# preamp.net
KiCad netlist of a schematic drawn in EAGLE
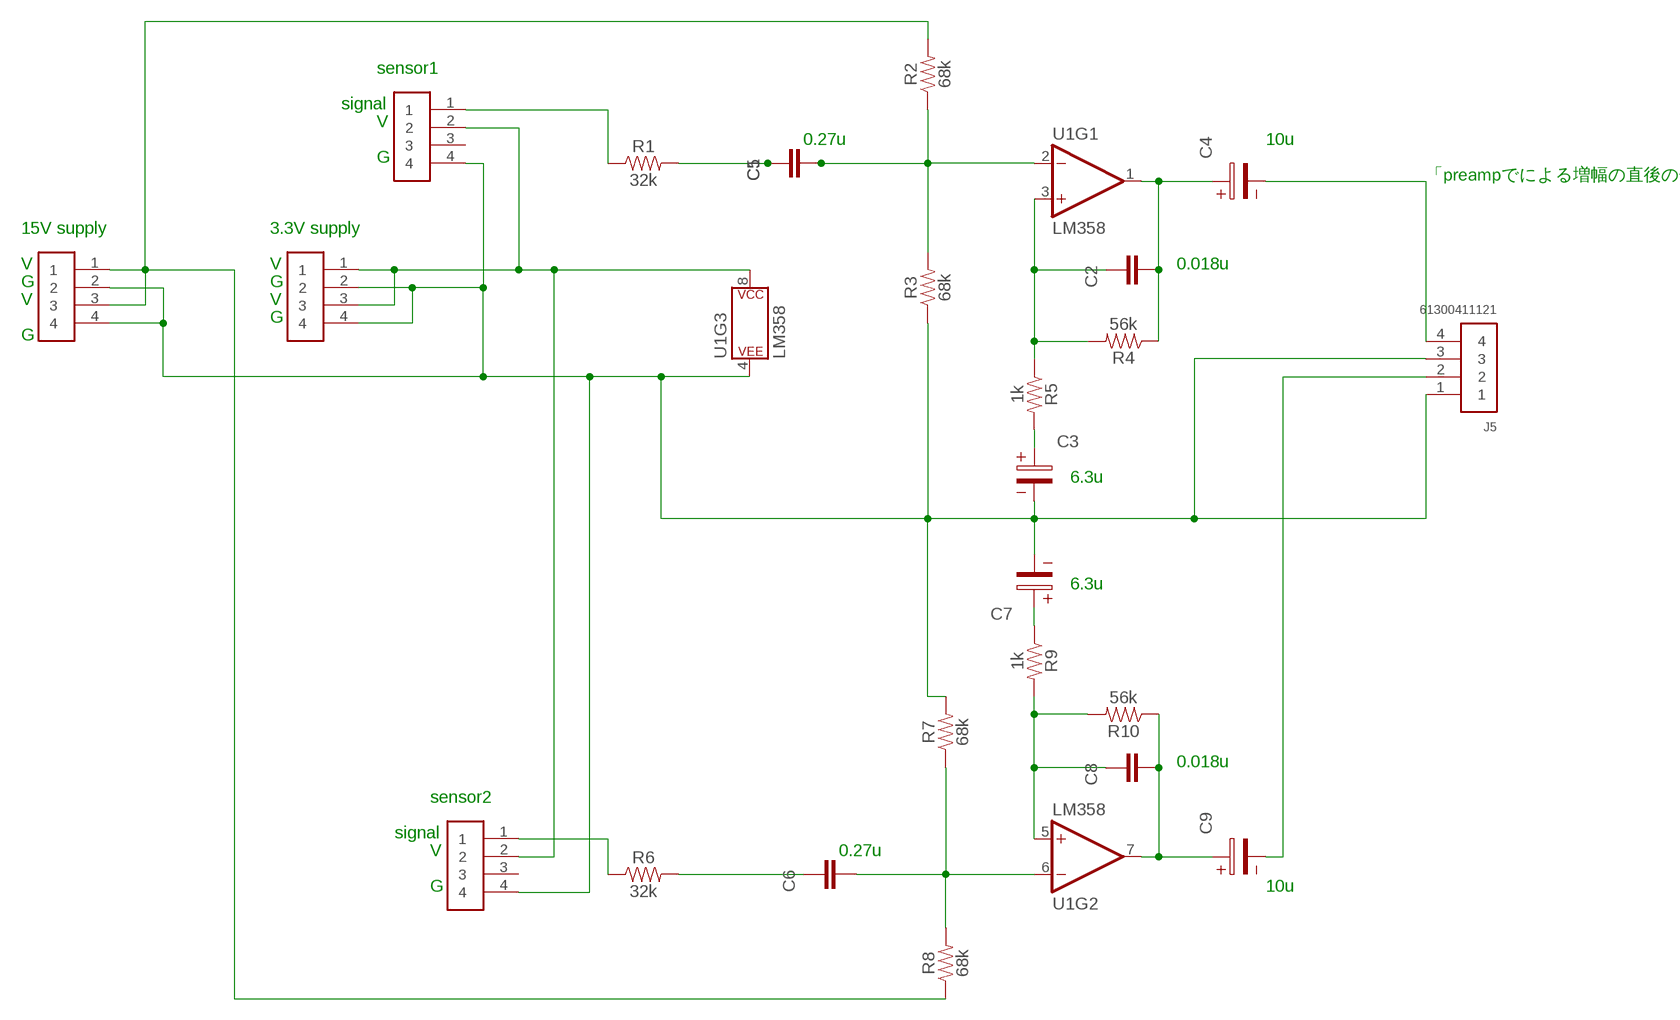
[diagram p0: schematic, sheet 1]

(export (version "E")
  (design (tool "Eeschema 10.0.6"))
  (components
    (comp (ref "C1")
      (value "CC0603JRNPO9BN270")
      (footprint "eagle-import:CAP_0603")
      (fields
        (field (name "DIGIKEY_PART_NUMBER") "311-1063-2-ND")
        (field (name "MANUFACTURER") "Yageo")
        (field (name "CREATED_BY") "PCBLayout.com")
      )
      (libsource (lib "eagle-import") (part "CC0603JRNPO9BN270"))
    )
    (comp (ref "C2")
      (value "0.018u")
      (footprint "eagle-import:CAP_0603")
      (fields
        (field (name "DIGIKEY_PART_NUMBER") "311-1063-2-ND")
        (field (name "MANUFACTURER") "Yageo")
        (field (name "MPN") "CC0603JRNPO9BN270")
        (field (name "CREATED_BY") "PCBLayout.com")
      )
      (libsource (lib "eagle-import") (part "CC0603JRNPO9BN270"))
    )
    (comp (ref "C3")
      (value "WCAP-AI3H_25X30_861141084008")
      (footprint "eagle-import:25X10X2(DXPXΦ)")
      (libsource (lib "eagle-import") (part "WCAP-AI3H_861141084008_25X30"))
    )
    (comp (ref "C4")
      (value "WCAP-AI3H_25X30_861141084008")
      (footprint "eagle-import:25X10X2(DXPXΦ)")
      (libsource (lib "eagle-import") (part "WCAP-AI3H_861141084008_25X30"))
    )
    (comp (ref "C5")
      (value "0.27u")
      (footprint "eagle-import:CAP_0603")
      (fields
        (field (name "DIGIKEY_PART_NUMBER") "311-1063-2-ND")
        (field (name "MANUFACTURER") "Yageo")
        (field (name "MPN") "CC0603JRNPO9BN270")
        (field (name "CREATED_BY") "PCBLayout.com")
      )
      (libsource (lib "eagle-import") (part "CC0603JRNPO9BN270"))
    )
    (comp (ref "C6")
      (value "CC0603JRNPO9BN270")
      (footprint "eagle-import:CAP_0603")
      (fields
        (field (name "DIGIKEY_PART_NUMBER") "311-1063-2-ND")
        (field (name "MANUFACTURER") "Yageo")
        (field (name "CREATED_BY") "PCBLayout.com")
      )
      (libsource (lib "eagle-import") (part "CC0603JRNPO9BN270"))
    )
    (comp (ref "C7")
      (value "WCAP-AI3H_25X30_861141084008")
      (footprint "eagle-import:25X10X2(DXPXΦ)")
      (libsource (lib "eagle-import") (part "WCAP-AI3H_861141084008_25X30"))
    )
    (comp (ref "C8")
      (value "CC0603JRNPO9BN270")
      (footprint "eagle-import:CAP_0603")
      (fields
        (field (name "DIGIKEY_PART_NUMBER") "311-1063-2-ND")
        (field (name "MANUFACTURER") "Yageo")
        (field (name "CREATED_BY") "PCBLayout.com")
      )
      (libsource (lib "eagle-import") (part "CC0603JRNPO9BN270"))
    )
    (comp (ref "C9")
      (value "WCAP-AI3H_25X30_861141084008")
      (footprint "eagle-import:25X10X2(DXPXΦ)")
      (libsource (lib "eagle-import") (part "WCAP-AI3H_861141084008_25X30"))
    )
    (comp (ref "J1")
      (value "61300411121")
      (footprint "eagle-import:61300411121")
      (fields
        (field (name "DIGI_KEY_PART_NUMBER") "732-5317-ND")
        (field (name "MANUFACTURER") "Wurth Electronics Inc.")
        (field (name "CREATED_BY") "PCBLayout.com")
      )
      (libsource (lib "eagle-import") (part "61300411121"))
    )
    (comp (ref "J2")
      (value "61300411121")
      (footprint "eagle-import:61300411121")
      (fields
        (field (name "DIGI_KEY_PART_NUMBER") "732-5317-ND")
        (field (name "MANUFACTURER") "Wurth Electronics Inc.")
        (field (name "CREATED_BY") "PCBLayout.com")
      )
      (libsource (lib "eagle-import") (part "61300411121"))
    )
    (comp (ref "J3")
      (value "61300411121")
      (footprint "eagle-import:61300411121")
      (fields
        (field (name "DIGI_KEY_PART_NUMBER") "732-5317-ND")
        (field (name "MANUFACTURER") "Wurth Electronics Inc.")
        (field (name "CREATED_BY") "PCBLayout.com")
      )
      (libsource (lib "eagle-import") (part "61300411121"))
    )
    (comp (ref "J4")
      (value "61300411121")
      (footprint "eagle-import:61300411121")
      (fields
        (field (name "DIGI_KEY_PART_NUMBER") "732-5317-ND")
        (field (name "MANUFACTURER") "Wurth Electronics Inc.")
        (field (name "CREATED_BY") "PCBLayout.com")
      )
      (libsource (lib "eagle-import") (part "61300411121"))
    )
    (comp (ref "J5")
      (value "61300411121")
      (footprint "eagle-import:61300411121")
      (fields
        (field (name "DIGI_KEY_PART_NUMBER") "732-5317-ND")
        (field (name "MANUFACTURER") "Wurth Electronics Inc.")
        (field (name "CREATED_BY") "PCBLayout.com")
      )
      (libsource (lib "eagle-import") (part "61300411121"))
    )
    (comp (ref "R1")
      (value "32k")
      (footprint "eagle-import:AXIAL-0.3")
      (libsource (lib "eagle-import") (part "10MOHM-HORIZ-1/4W-5%"))
    )
    (comp (ref "R2")
      (value "68k")
      (footprint "eagle-import:AXIAL-0.3")
      (libsource (lib "eagle-import") (part "10MOHM-HORIZ-1/4W-5%"))
    )
    (comp (ref "R3")
      (value "68k")
      (footprint "eagle-import:AXIAL-0.3")
      (libsource (lib "eagle-import") (part "10MOHM-HORIZ-1/4W-5%"))
    )
    (comp (ref "R4")
      (value "56k")
      (footprint "eagle-import:AXIAL-0.3")
      (libsource (lib "eagle-import") (part "10MOHM-HORIZ-1/4W-5%"))
    )
    (comp (ref "R5")
      (value "1k")
      (footprint "eagle-import:AXIAL-0.3")
      (libsource (lib "eagle-import") (part "10MOHM-HORIZ-1/4W-5%"))
    )
    (comp (ref "R6")
      (value "32k")
      (footprint "eagle-import:AXIAL-0.3")
      (libsource (lib "eagle-import") (part "10MOHM-HORIZ-1/4W-5%"))
    )
    (comp (ref "R7")
      (value "68k")
      (footprint "eagle-import:AXIAL-0.3")
      (libsource (lib "eagle-import") (part "10MOHM-HORIZ-1/4W-5%"))
    )
    (comp (ref "R8")
      (value "68k")
      (footprint "eagle-import:AXIAL-0.3")
      (libsource (lib "eagle-import") (part "10MOHM-HORIZ-1/4W-5%"))
    )
    (comp (ref "R9")
      (value "1k")
      (footprint "eagle-import:AXIAL-0.3")
      (libsource (lib "eagle-import") (part "10MOHM-HORIZ-1/4W-5%"))
    )
    (comp (ref "R10")
      (value "56k")
      (footprint "eagle-import:AXIAL-0.3")
      (libsource (lib "eagle-import") (part "10MOHM-HORIZ-1/4W-5%"))
    )
    (comp (ref "U1")
      (value "LM358")
      (footprint "eagle-import:DIP08")
      (libsource (lib "eagle-import") (part "LM358"))
    )
  )
  (nets
    (net (code "1") (name "Net-(C4-Pad2)") (class "Default")
      (node (ref "C4") (pin "2") (pinfunction "2_2") (pintype "passive"))
      (node (ref "J5") (pin "4") (pinfunction "4_4") (pintype "passive"))
    )
    (net (code "2") (name "Net-(C9-Pad2)") (class "Default")
      (node (ref "C9") (pin "2") (pinfunction "2_2") (pintype "passive"))
      (node (ref "J5") (pin "2") (pinfunction "2_2") (pintype "passive"))
    )
    (net (code "3") (name "Net-(R1-1)") (class "Default")
      (node (ref "J3") (pin "1") (pinfunction "1_1") (pintype "passive"))
      (node (ref "R1") (pin "P$1") (pinfunction "1_P$1") (pintype "passive"))
    )
    (net (code "4") (name "Net-(R1-2)") (class "Default")
      (node (ref "C1") (pin "1") (pinfunction "1_1") (pintype "passive"))
      (node (ref "C5") (pin "1") (pinfunction "1_1") (pintype "passive"))
      (node (ref "R1") (pin "P$2") (pinfunction "2_P$2") (pintype "passive"))
    )
    (net (code "5") (name "Net-(R2-1)") (class "Default")
      (node (ref "C1") (pin "2") (pinfunction "2_2") (pintype "passive"))
      (node (ref "C5") (pin "2") (pinfunction "2_2") (pintype "passive"))
      (node (ref "R2") (pin "P$1") (pinfunction "1_P$1") (pintype "passive"))
      (node (ref "R3") (pin "P$2") (pinfunction "2_P$2") (pintype "passive"))
      (node (ref "U1") (pin "2") (pinfunction "-IN_2") (pintype "input"))
    )
    (net (code "6") (name "Net-(R2-2)") (class "Default")
      (node (ref "J4") (pin "1") (pinfunction "1_1") (pintype "passive"))
      (node (ref "J4") (pin "3") (pinfunction "3_3") (pintype "passive"))
      (node (ref "R2") (pin "P$2") (pinfunction "2_P$2") (pintype "passive"))
      (node (ref "R8") (pin "P$1") (pinfunction "1_P$1") (pintype "passive"))
    )
    (net (code "7") (name "Net-(R3-1)") (class "Default")
      (node (ref "C3") (pin "2") (pinfunction "2_2") (pintype "passive"))
      (node (ref "C7") (pin "2") (pinfunction "2_2") (pintype "passive"))
      (node (ref "J1") (pin "2") (pinfunction "2_2") (pintype "passive"))
      (node (ref "J1") (pin "4") (pinfunction "4_4") (pintype "passive"))
      (node (ref "J2") (pin "4") (pinfunction "4_4") (pintype "passive"))
      (node (ref "J3") (pin "4") (pinfunction "4_4") (pintype "passive"))
      (node (ref "J4") (pin "2") (pinfunction "2_2") (pintype "passive"))
      (node (ref "J4") (pin "4") (pinfunction "4_4") (pintype "passive"))
      (node (ref "J5") (pin "1") (pinfunction "1_1") (pintype "passive"))
      (node (ref "J5") (pin "3") (pinfunction "3_3") (pintype "passive"))
      (node (ref "R3") (pin "P$1") (pinfunction "1_P$1") (pintype "passive"))
      (node (ref "R7") (pin "P$2") (pinfunction "2_P$2") (pintype "passive"))
      (node (ref "U1") (pin "4") (pinfunction "P$V-_4") (pintype "bidirectional"))
    )
    (net (code "8") (name "Net-(R4-1)") (class "Default")
      (node (ref "C2") (pin "2") (pinfunction "2_2") (pintype "passive"))
      (node (ref "C4") (pin "1") (pinfunction "1_1") (pintype "passive"))
      (node (ref "R4") (pin "P$1") (pinfunction "1_P$1") (pintype "passive"))
      (node (ref "U1") (pin "1") (pinfunction "OUT_1") (pintype "output"))
    )
    (net (code "9") (name "Net-(R4-2)") (class "Default")
      (node (ref "C2") (pin "1") (pinfunction "1_1") (pintype "passive"))
      (node (ref "R4") (pin "P$2") (pinfunction "2_P$2") (pintype "passive"))
      (node (ref "R5") (pin "P$1") (pinfunction "1_P$1") (pintype "passive"))
      (node (ref "U1") (pin "3") (pinfunction "+IN_3") (pintype "input"))
    )
    (net (code "10") (name "Net-(R5-2)") (class "Default")
      (node (ref "C3") (pin "1") (pinfunction "1_1") (pintype "passive"))
      (node (ref "R5") (pin "P$2") (pinfunction "2_P$2") (pintype "passive"))
    )
    (net (code "11") (name "Net-(R6-1)") (class "Default")
      (node (ref "J2") (pin "1") (pinfunction "1_1") (pintype "passive"))
      (node (ref "R6") (pin "P$1") (pinfunction "1_P$1") (pintype "passive"))
    )
    (net (code "12") (name "Net-(R6-2)") (class "Default")
      (node (ref "C6") (pin "1") (pinfunction "1_1") (pintype "passive"))
      (node (ref "R6") (pin "P$2") (pinfunction "2_P$2") (pintype "passive"))
    )
    (net (code "13") (name "Net-(R7-1)") (class "Default")
      (node (ref "C6") (pin "2") (pinfunction "2_2") (pintype "passive"))
      (node (ref "R7") (pin "P$1") (pinfunction "1_P$1") (pintype "passive"))
      (node (ref "R8") (pin "P$2") (pinfunction "2_P$2") (pintype "passive"))
      (node (ref "U1") (pin "6") (pinfunction "-IN_6") (pintype "input"))
    )
    (net (code "14") (name "Net-(R9-1)") (class "Default")
      (node (ref "C7") (pin "1") (pinfunction "1_1") (pintype "passive"))
      (node (ref "R9") (pin "P$1") (pinfunction "1_P$1") (pintype "passive"))
    )
    (net (code "15") (name "Net-(R10-1)") (class "Default")
      (node (ref "C8") (pin "2") (pinfunction "2_2") (pintype "passive"))
      (node (ref "C9") (pin "1") (pinfunction "1_1") (pintype "passive"))
      (node (ref "R10") (pin "P$1") (pinfunction "1_P$1") (pintype "passive"))
      (node (ref "U1") (pin "7") (pinfunction "OUT_7") (pintype "output"))
    )
    (net (code "16") (name "Net-(R10-2)") (class "Default")
      (node (ref "C8") (pin "1") (pinfunction "1_1") (pintype "passive"))
      (node (ref "R10") (pin "P$2") (pinfunction "2_P$2") (pintype "passive"))
      (node (ref "R9") (pin "P$2") (pinfunction "2_P$2") (pintype "passive"))
      (node (ref "U1") (pin "5") (pinfunction "+IN_5") (pintype "input"))
    )
    (net (code "17") (name "Net-(U1C-P$V+)") (class "Default")
      (node (ref "J1") (pin "1") (pinfunction "1_1") (pintype "passive"))
      (node (ref "J1") (pin "3") (pinfunction "3_3") (pintype "passive"))
      (node (ref "J2") (pin "2") (pinfunction "2_2") (pintype "passive"))
      (node (ref "J3") (pin "2") (pinfunction "2_2") (pintype "passive"))
      (node (ref "U1") (pin "8") (pinfunction "P$V+_8") (pintype "bidirectional"))
    )
    (net (code "18") (name "unconnected-(J2-Pad3)") (class "Default")
      (node (ref "J2") (pin "3") (pinfunction "3_3") (pintype "passive"))
    )
    (net (code "19") (name "unconnected-(J3-Pad3)") (class "Default")
      (node (ref "J3") (pin "3") (pinfunction "3_3") (pintype "passive"))
    )
  )
)
